# Spectacle_Director_Board.net
KiCad netlist of a schematic drawn in EAGLE
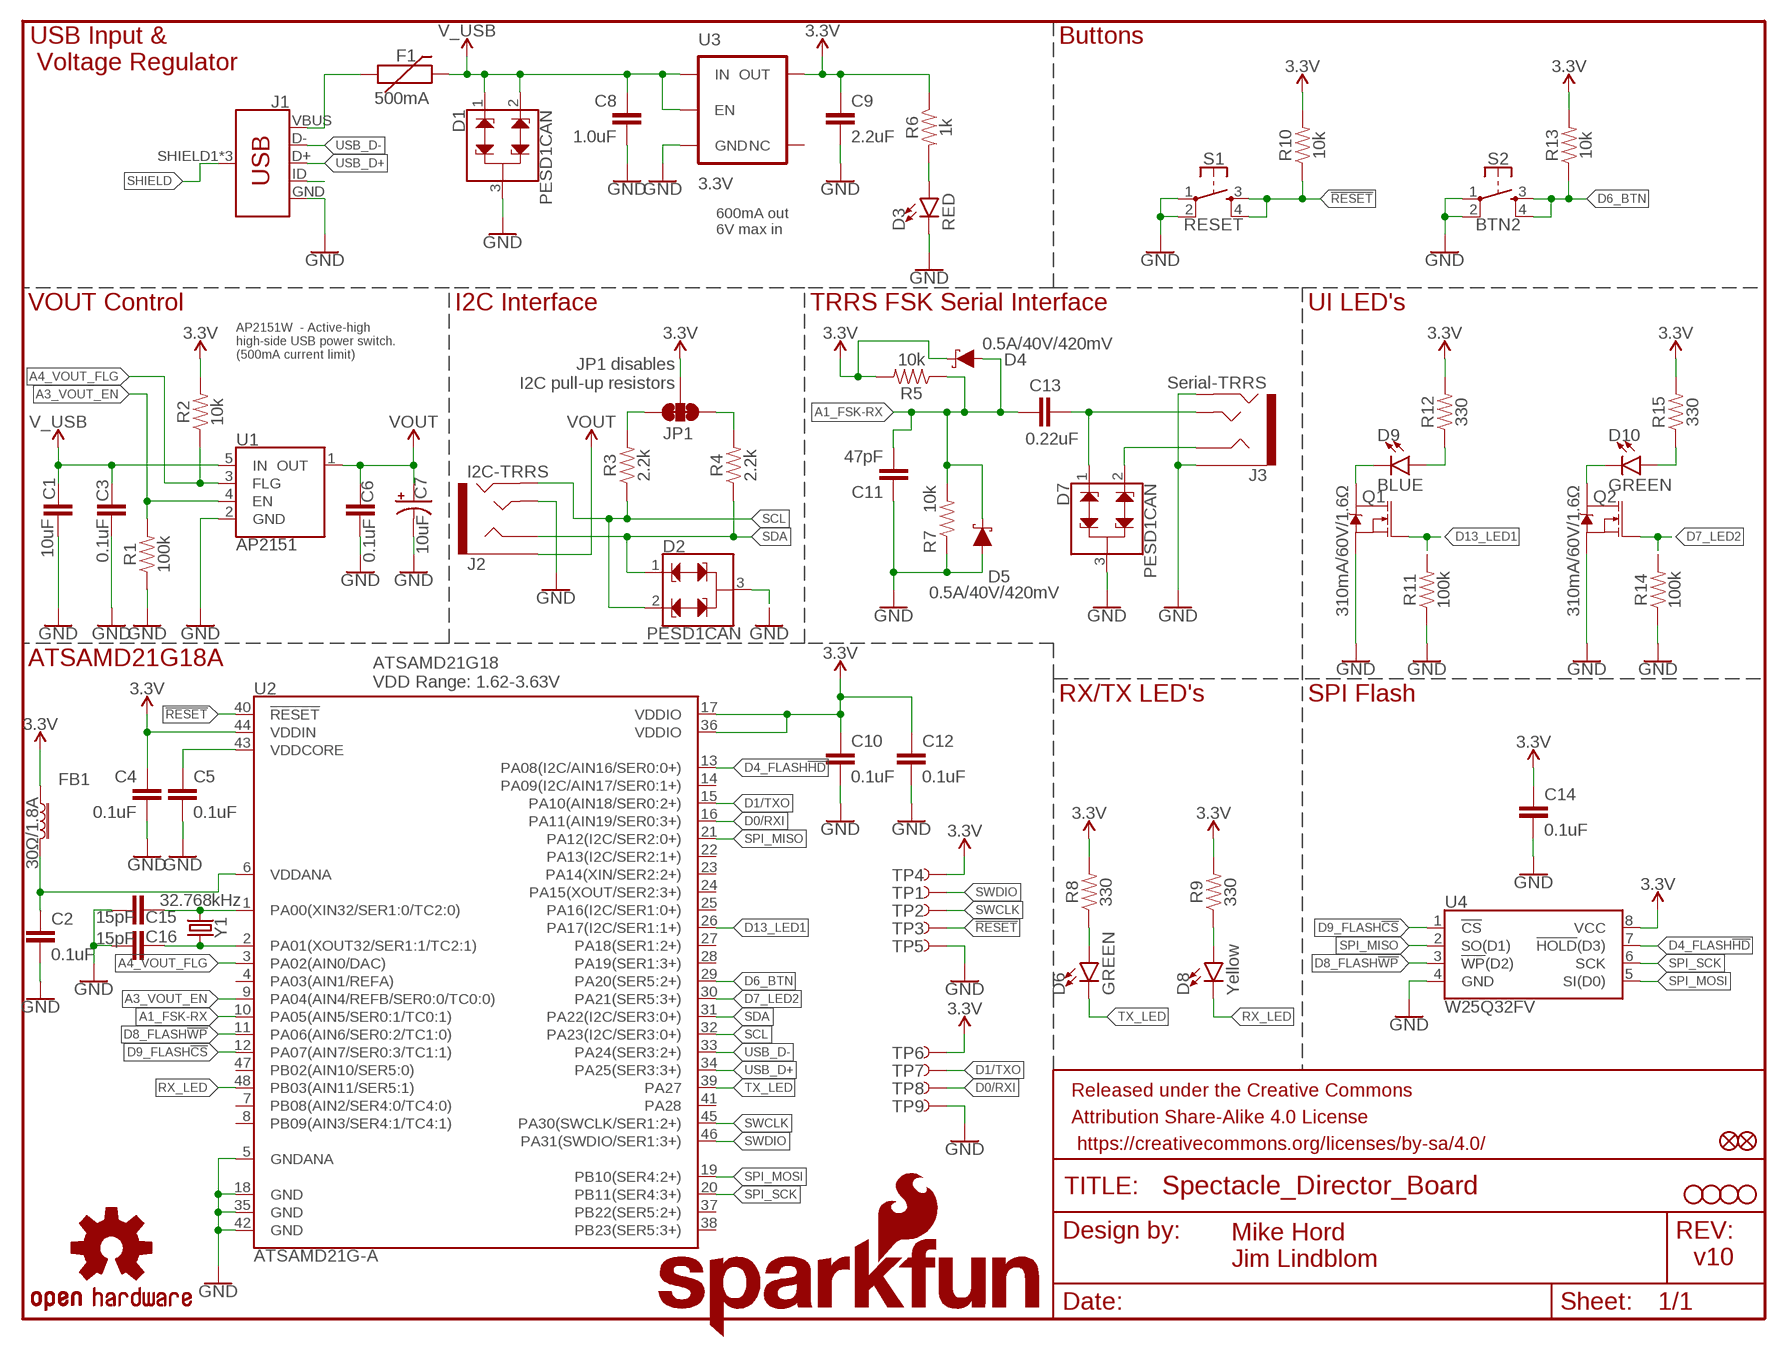
[diagram p0: schematic, sheet 1]

(export (version "E")
  (design (tool "Eeschema 10.0.6"))
  (components
    (comp (ref "C1")
      (value "10uF")
      (footprint "eagle-import:0805")
      (libsource (lib "eagle-import") (part "10UF-0805-10V-10%"))
    )
    (comp (ref "C2")
      (value "0.1uF")
      (footprint "eagle-import:0603")
      (libsource (lib "eagle-import") (part "0.1UF-0603-25V-(+80/-20%)"))
    )
    (comp (ref "C3")
      (value "0.1uF")
      (footprint "eagle-import:0603")
      (libsource (lib "eagle-import") (part "0.1UF-0603-25V-(+80/-20%)"))
    )
    (comp (ref "C4")
      (value "0.1uF")
      (footprint "eagle-import:0603")
      (libsource (lib "eagle-import") (part "0.1UF-0603-25V-(+80/-20%)"))
    )
    (comp (ref "C5")
      (value "0.1uF")
      (footprint "eagle-import:0603")
      (libsource (lib "eagle-import") (part "0.1UF-0603-25V-(+80/-20%)"))
    )
    (comp (ref "C6")
      (value "0.1uF")
      (footprint "eagle-import:0603")
      (libsource (lib "eagle-import") (part "0.1UF-0603-25V-(+80/-20%)"))
    )
    (comp (ref "C7")
      (value "10uF")
      (footprint "eagle-import:EIA3216")
      (libsource (lib "eagle-import") (part "10UF-POLAR-EIA3216-16V-10%(TANT)"))
    )
    (comp (ref "C8")
      (value "1.0uF")
      (footprint "eagle-import:0805")
      (libsource (lib "eagle-import") (part "1.0UF-0805-25V-(+80/-20%)"))
    )
    (comp (ref "C9")
      (value "2.2uF")
      (footprint "eagle-import:0603")
      (libsource (lib "eagle-import") (part "2.2UF-0603-10V-20%"))
    )
    (comp (ref "C10")
      (value "0.1uF")
      (footprint "eagle-import:0603")
      (libsource (lib "eagle-import") (part "0.1UF-0603-25V-(+80/-20%)"))
    )
    (comp (ref "C11")
      (value "47pF")
      (footprint "eagle-import:0603")
      (libsource (lib "eagle-import") (part "47PF-0603-50V-5%"))
    )
    (comp (ref "C12")
      (value "0.1uF")
      (footprint "eagle-import:0603")
      (libsource (lib "eagle-import") (part "0.1UF-0603-25V-(+80/-20%)"))
    )
    (comp (ref "C13")
      (value "0.22uF")
      (footprint "eagle-import:0603")
      (libsource (lib "eagle-import") (part "0.22UF-0603-25V-10%"))
    )
    (comp (ref "C14")
      (value "0.1uF")
      (footprint "eagle-import:0603")
      (libsource (lib "eagle-import") (part "0.1UF-0603-25V-(+80/-20%)"))
    )
    (comp (ref "C15")
      (value "15pF")
      (footprint "eagle-import:0603")
      (libsource (lib "eagle-import") (part "15PF-0603-50V-5%"))
    )
    (comp (ref "C16")
      (value "15pF")
      (footprint "eagle-import:0603")
      (libsource (lib "eagle-import") (part "15PF-0603-50V-5%"))
    )
    (comp (ref "D1")
      (value "PESD1CAN")
      (footprint "eagle-import:SOT23-3")
      (libsource (lib "eagle-import") (part "PESD1CAN"))
    )
    (comp (ref "D2")
      (value "PESD1CAN")
      (footprint "eagle-import:SOT23-3")
      (libsource (lib "eagle-import") (part "PESD1CAN"))
    )
    (comp (ref "D3")
      (value "RED")
      (footprint "eagle-import:LED-0603")
      (libsource (lib "eagle-import") (part "LED-RED0603"))
    )
    (comp (ref "D4")
      (value "0.5A/40V/420mV")
      (footprint "eagle-import:SOD-323")
      (libsource (lib "eagle-import") (part "DIODE-SCHOTTKY-PMEG4005EJ"))
    )
    (comp (ref "D5")
      (value "0.5A/40V/420mV")
      (footprint "eagle-import:SOD-323")
      (libsource (lib "eagle-import") (part "DIODE-SCHOTTKY-PMEG4005EJ"))
    )
    (comp (ref "D6")
      (value "GREEN")
      (footprint "eagle-import:LED-0603")
      (libsource (lib "eagle-import") (part "LED-GREEN0603"))
    )
    (comp (ref "D7")
      (value "PESD1CAN")
      (footprint "eagle-import:SOT23-3")
      (libsource (lib "eagle-import") (part "PESD1CAN"))
    )
    (comp (ref "D8")
      (value "Yellow")
      (footprint "eagle-import:LED-0603")
      (libsource (lib "eagle-import") (part "LED-YELLOW0603"))
    )
    (comp (ref "D9")
      (value "BLUE")
      (footprint "eagle-import:LED-0603")
      (libsource (lib "eagle-import") (part "LED-BLUE0603"))
    )
    (comp (ref "D10")
      (value "GREEN")
      (footprint "eagle-import:LED-0603")
      (libsource (lib "eagle-import") (part "LED-GREEN0603"))
    )
    (comp (ref "F1")
      (value "500mA")
      (footprint "eagle-import:PTC-1206")
      (libsource (lib "eagle-import") (part "PTCSMD"))
    )
    (comp (ref "FB1")
      (value "30Ω/1.8A")
      (footprint "eagle-import:0603")
      (libsource (lib "eagle-import") (part "FERRITE_BEAD-0603"))
    )
    (comp (ref "FD1")
      (value "FIDUCIALUFIDUCIAL")
      (footprint "eagle-import:FIDUCIAL-MICRO")
      (libsource (lib "eagle-import") (part "FIDUCIALUFIDUCIAL"))
    )
    (comp (ref "FD2")
      (value "FIDUCIALUFIDUCIAL")
      (footprint "eagle-import:FIDUCIAL-MICRO")
      (libsource (lib "eagle-import") (part "FIDUCIALUFIDUCIAL"))
    )
    (comp (ref "FRAME1")
      (value "FRAME-LETTER")
      (footprint "eagle-import:CREATIVE_COMMONS")
      (libsource (lib "eagle-import") (part "FRAME-LETTER"))
    )
    (comp (ref "H1")
      (value "STAND-OFF")
      (footprint "eagle-import:STAND-OFF")
      (libsource (lib "eagle-import") (part "STAND-OFF"))
    )
    (comp (ref "H2")
      (value "STAND-OFF")
      (footprint "eagle-import:STAND-OFF")
      (libsource (lib "eagle-import") (part "STAND-OFF"))
    )
    (comp (ref "H3")
      (value "STAND-OFF")
      (footprint "eagle-import:STAND-OFF")
      (libsource (lib "eagle-import") (part "STAND-OFF"))
    )
    (comp (ref "H4")
      (value "STAND-OFF")
      (footprint "eagle-import:STAND-OFF")
      (libsource (lib "eagle-import") (part "STAND-OFF"))
    )
    (comp (ref "J1")
      (value "USB_MICRO-B_FEMALE-SMT")
      (footprint "eagle-import:USB-B-MICRO-SMD")
      (libsource (lib "eagle-import") (part "USB_MICRO-B_FEMALE-SMT"))
    )
    (comp (ref "J2")
      (value "I2C-TRRS")
      (footprint "eagle-import:AUDIO_JACK_3.5MM_TRRS_SMD_RA")
      (libsource (lib "eagle-import") (part "AUDIO_JACK_TRRSSMD_RA"))
    )
    (comp (ref "J3")
      (value "Serial-TRRS")
      (footprint "eagle-import:AUDIO_JACK_3.5MM_TRRS_SMD_RA")
      (libsource (lib "eagle-import") (part "AUDIO_JACK_TRRSSMD_RA"))
    )
    (comp (ref "JP1")
      (value "JUMPER-SMT_3_2-NC_TRACE_NO-SILK")
      (footprint "eagle-import:SMT-JUMPER_3_2-NC_TRACE_NO-SILK")
      (libsource (lib "eagle-import") (part "JUMPER-SMT_3_2-NC_TRACE_NO-SILK"))
    )
    (comp (ref "LOGO1")
      (value "OSHW-LOGOMINI")
      (footprint "eagle-import:OSHW-LOGO-MINI")
      (libsource (lib "eagle-import") (part "OSHW-LOGOMINI"))
    )
    (comp (ref "LOGO2")
      (value "SFE_LOGO_NAME.2_INCH")
      (footprint "eagle-import:SFE_LOGO_NAME_.2")
      (libsource (lib "eagle-import") (part "SFE_LOGO_NAME.2_INCH"))
    )
    (comp (ref "LOGO3")
      (value "SFE_LOGO_FLAME.1COP")
      (footprint "eagle-import:SFE_LOGO_FLAME_COPPER_.1")
      (libsource (lib "eagle-import") (part "SFE_LOGO_FLAME.1COP"))
    )
    (comp (ref "Q1")
      (value "310mA/60V/1.6Ω")
      (footprint "eagle-import:SOT323")
      (libsource (lib "eagle-import") (part "MOSFET-NCH-2N7002PW"))
    )
    (comp (ref "Q2")
      (value "310mA/60V/1.6Ω")
      (footprint "eagle-import:SOT323")
      (libsource (lib "eagle-import") (part "MOSFET-NCH-2N7002PW"))
    )
    (comp (ref "R1")
      (value "100k")
      (footprint "eagle-import:0603")
      (libsource (lib "eagle-import") (part "100KOHM-0603-1/10W-1%"))
    )
    (comp (ref "R2")
      (value "10k")
      (footprint "eagle-import:0603")
      (libsource (lib "eagle-import") (part "10KOHM-0603-1/10W-1%"))
    )
    (comp (ref "R3")
      (value "2.2k")
      (footprint "eagle-import:0603")
      (libsource (lib "eagle-import") (part "2.2KOHM-0603-1/10W-1%"))
    )
    (comp (ref "R4")
      (value "2.2k")
      (footprint "eagle-import:0603")
      (libsource (lib "eagle-import") (part "2.2KOHM-0603-1/10W-1%"))
    )
    (comp (ref "R5")
      (value "10k")
      (footprint "eagle-import:0603")
      (libsource (lib "eagle-import") (part "10KOHM-0603-1/10W-1%"))
    )
    (comp (ref "R6")
      (value "1k")
      (footprint "eagle-import:0603")
      (libsource (lib "eagle-import") (part "1KOHM-0603-1/10W-1%"))
    )
    (comp (ref "R7")
      (value "10k")
      (footprint "eagle-import:0603")
      (libsource (lib "eagle-import") (part "10KOHM-0603-1/10W-1%"))
    )
    (comp (ref "R8")
      (value "330")
      (footprint "eagle-import:0603")
      (libsource (lib "eagle-import") (part "330OHM-0603-1/10W-1%"))
    )
    (comp (ref "R9")
      (value "330")
      (footprint "eagle-import:0603")
      (libsource (lib "eagle-import") (part "330OHM-0603-1/10W-1%"))
    )
    (comp (ref "R10")
      (value "10k")
      (footprint "eagle-import:0603")
      (libsource (lib "eagle-import") (part "10KOHM-0603-1/10W-1%"))
    )
    (comp (ref "R11")
      (value "100k")
      (footprint "eagle-import:0603")
      (libsource (lib "eagle-import") (part "100KOHM-0603-1/10W-1%"))
    )
    (comp (ref "R12")
      (value "330")
      (footprint "eagle-import:0603")
      (libsource (lib "eagle-import") (part "330OHM-0603-1/10W-1%"))
    )
    (comp (ref "R13")
      (value "10k")
      (footprint "eagle-import:0603")
      (libsource (lib "eagle-import") (part "10KOHM-0603-1/10W-1%"))
    )
    (comp (ref "R14")
      (value "100k")
      (footprint "eagle-import:0603")
      (libsource (lib "eagle-import") (part "100KOHM-0603-1/10W-1%"))
    )
    (comp (ref "R15")
      (value "330")
      (footprint "eagle-import:0603")
      (libsource (lib "eagle-import") (part "330OHM-0603-1/10W-1%"))
    )
    (comp (ref "S1")
      (value "RESET")
      (footprint "eagle-import:TACTILE_SWITCH_SMD_4.6X2.8MM")
      (libsource (lib "eagle-import") (part "MOMENTARY-SWITCH-SPST-2-SMD-4.6X2.8MM"))
    )
    (comp (ref "S2")
      (value "BTN2")
      (footprint "eagle-import:TACTILE_SWITCH_SMD_4.6X2.8MM")
      (libsource (lib "eagle-import") (part "MOMENTARY-SWITCH-SPST-2-SMD-4.6X2.8MM"))
    )
    (comp (ref "TP1")
      (value "TP-SWDIO")
      (footprint "eagle-import:PAD.03X.05")
      (libsource (lib "eagle-import") (part "TEST-POINT3X5"))
    )
    (comp (ref "TP2")
      (value "TP-SWCLK")
      (footprint "eagle-import:PAD.03X.05")
      (libsource (lib "eagle-import") (part "TEST-POINT3X5"))
    )
    (comp (ref "TP3")
      (value "TP-!RESET!")
      (footprint "eagle-import:PAD.03X.05")
      (libsource (lib "eagle-import") (part "TEST-POINT3X5"))
    )
    (comp (ref "TP4")
      (value "TP-3.3V")
      (footprint "eagle-import:PAD.03X.05")
      (libsource (lib "eagle-import") (part "TEST-POINT3X5"))
    )
    (comp (ref "TP5")
      (value "TP-GND")
      (footprint "eagle-import:PAD.03X.05")
      (libsource (lib "eagle-import") (part "TEST-POINT3X5"))
    )
    (comp (ref "TP6")
      (value "TP-GND")
      (footprint "eagle-import:PAD.03X.05")
      (libsource (lib "eagle-import") (part "TEST-POINT3X5"))
    )
    (comp (ref "TP7")
      (value "TP-GND")
      (footprint "eagle-import:PAD.03X.05")
      (libsource (lib "eagle-import") (part "TEST-POINT3X5"))
    )
    (comp (ref "TP8")
      (value "TP-GND")
      (footprint "eagle-import:PAD.03X.05")
      (libsource (lib "eagle-import") (part "TEST-POINT3X5"))
    )
    (comp (ref "TP9")
      (value "TP-GND")
      (footprint "eagle-import:PAD.03X.05")
      (libsource (lib "eagle-import") (part "TEST-POINT3X5"))
    )
    (comp (ref "U1")
      (value "AP2151")
      (footprint "eagle-import:SOT23-5")
      (libsource (lib "eagle-import") (part "AP2151W"))
    )
    (comp (ref "U2")
      (value "ATSAMD21G-A")
      (footprint "eagle-import:TQFP-48")
      (libsource (lib "eagle-import") (part "ATSAMD21G-A"))
    )
    (comp (ref "U3")
      (value "3.3V")
      (footprint "eagle-import:SOT23-5")
      (fields (field (name "PROD_ID") "VREG-12457"))
      (libsource (lib "eagle-import") (part "V_REG_AP2112K-3.3V"))
    )
    (comp (ref "U4")
      (value "W25Q32FV")
      (footprint "eagle-import:SOIC-8")
      (libsource (lib "eagle-import") (part "W25Q32FVSS"))
    )
    (comp (ref "Y1")
      (value "32.768kHz")
      (footprint "eagle-import:CRYSTAL-SMD-3.2X1.5MM")
      (libsource (lib "eagle-import") (part "CRYSTAL-32.768KHZSMD-3.2X1.5"))
    )
  )
  (nets
    (net (code "1") (name "/D4_FLASH~{HD}") (class "Default")
      (node (ref "U2") (pin "13") (pinfunction "PA08(I2C/AIN16/SER0:0+)_13") (pintype "bidirectional"))
      (node (ref "U4") (pin "7") (pinfunction "~{HOLD}(D3)_7") (pintype "bidirectional"))
    )
    (net (code "2") (name "/D8_FLASH~{WP}") (class "Default")
      (node (ref "U2") (pin "11") (pinfunction "PA06(AIN6/SER0:2/TC1:0)_11") (pintype "bidirectional"))
      (node (ref "U4") (pin "3") (pinfunction "~{WP}(D2)_3") (pintype "bidirectional"))
    )
    (net (code "3") (name "/D9_FLASH~{CS}") (class "Default")
      (node (ref "U2") (pin "12") (pinfunction "PA07(AIN7/SER0:3/TC1:1)_12") (pintype "bidirectional"))
      (node (ref "U4") (pin "1") (pinfunction "~{CS}_1") (pintype "bidirectional"))
    )
    (net (code "4") (name "/~{RESET}") (class "Default")
      (node (ref "R10") (pin "1") (pinfunction "1_1") (pintype "passive"))
      (node (ref "S1") (pin "3") (pinfunction "3_3") (pintype "passive"))
      (node (ref "S1") (pin "4") (pinfunction "4_4") (pintype "passive"))
      (node (ref "TP3") (pin "P$1") (pinfunction "1_P$1") (pintype "bidirectional"))
      (node (ref "U2") (pin "40") (pinfunction "~{RESET}_40") (pintype "bidirectional"))
    )
    (net (code "5") (name "3.3V") (class "Default")
      (node (ref "C10") (pin "1") (pinfunction "1_1") (pintype "passive"))
      (node (ref "C12") (pin "1") (pinfunction "1_1") (pintype "passive"))
      (node (ref "C14") (pin "1") (pinfunction "1_1") (pintype "passive"))
      (node (ref "C4") (pin "1") (pinfunction "1_1") (pintype "passive"))
      (node (ref "C9") (pin "1") (pinfunction "1_1") (pintype "passive"))
      (node (ref "D4") (pin "C") (pinfunction "C_C") (pintype "passive"))
      (node (ref "FB1") (pin "1") (pinfunction "1_1") (pintype "passive"))
      (node (ref "JP1") (pin "2") (pinfunction "2_2") (pintype "passive"))
      (node (ref "R10") (pin "2") (pinfunction "2_2") (pintype "passive"))
      (node (ref "R12") (pin "2") (pinfunction "2_2") (pintype "passive"))
      (node (ref "R13") (pin "2") (pinfunction "2_2") (pintype "passive"))
      (node (ref "R15") (pin "2") (pinfunction "2_2") (pintype "passive"))
      (node (ref "R2") (pin "2") (pinfunction "2_2") (pintype "passive"))
      (node (ref "R5") (pin "2") (pinfunction "2_2") (pintype "passive"))
      (node (ref "R6") (pin "1") (pinfunction "1_1") (pintype "passive"))
      (node (ref "R8") (pin "2") (pinfunction "2_2") (pintype "passive"))
      (node (ref "R9") (pin "2") (pinfunction "2_2") (pintype "passive"))
      (node (ref "TP4") (pin "P$1") (pinfunction "1_P$1") (pintype "bidirectional"))
      (node (ref "TP6") (pin "P$1") (pinfunction "1_P$1") (pintype "bidirectional"))
      (node (ref "U2") (pin "17") (pinfunction "VDDIO_17") (pintype "bidirectional"))
      (node (ref "U2") (pin "36") (pinfunction "VDDIO_36") (pintype "bidirectional"))
      (node (ref "U2") (pin "44") (pinfunction "VDDIN_44") (pintype "bidirectional"))
      (node (ref "U3") (pin "5") (pinfunction "OUT_5") (pintype "passive"))
      (node (ref "U4") (pin "8") (pinfunction "VCC_8") (pintype "bidirectional"))
    )
    (net (code "6") (name "A1_FSK-RX") (class "Default")
      (node (ref "C11") (pin "2") (pinfunction "2_2") (pintype "passive"))
      (node (ref "C13") (pin "1") (pinfunction "1_1") (pintype "passive"))
      (node (ref "D4") (pin "A") (pinfunction "A_A") (pintype "passive"))
      (node (ref "D5") (pin "C") (pinfunction "C_C") (pintype "passive"))
      (node (ref "R5") (pin "1") (pinfunction "1_1") (pintype "passive"))
      (node (ref "R7") (pin "2") (pinfunction "2_2") (pintype "passive"))
      (node (ref "U2") (pin "10") (pinfunction "PA05(AIN5/SER0:1/TC0:1)_10") (pintype "bidirectional"))
    )
    (net (code "7") (name "A3_VOUT_EN") (class "Default")
      (node (ref "R1") (pin "2") (pinfunction "2_2") (pintype "passive"))
      (node (ref "U1") (pin "4") (pinfunction "EN_4") (pintype "bidirectional"))
      (node (ref "U2") (pin "9") (pinfunction "PA04(AIN4/REFB/SER0:0/TC0:0)_9") (pintype "bidirectional"))
    )
    (net (code "8") (name "A4_VOUT_FLG") (class "Default")
      (node (ref "R2") (pin "1") (pinfunction "1_1") (pintype "passive"))
      (node (ref "U1") (pin "3") (pinfunction "FLG_3") (pintype "bidirectional"))
      (node (ref "U2") (pin "3") (pinfunction "PA02(AIN0/DAC)_3") (pintype "bidirectional"))
    )
    (net (code "9") (name "D0{slash}RXI") (class "Default")
      (node (ref "TP8") (pin "P$1") (pinfunction "1_P$1") (pintype "bidirectional"))
      (node (ref "U2") (pin "16") (pinfunction "PA11(AIN19/SER0:3+)_16") (pintype "bidirectional"))
    )
    (net (code "10") (name "D1{slash}TXO") (class "Default")
      (node (ref "TP7") (pin "P$1") (pinfunction "1_P$1") (pintype "bidirectional"))
      (node (ref "U2") (pin "15") (pinfunction "PA10(AIN18/SER0:2+)_15") (pintype "bidirectional"))
    )
    (net (code "11") (name "D6_BTN") (class "Default")
      (node (ref "R13") (pin "1") (pinfunction "1_1") (pintype "passive"))
      (node (ref "S2") (pin "3") (pinfunction "3_3") (pintype "passive"))
      (node (ref "S2") (pin "4") (pinfunction "4_4") (pintype "passive"))
      (node (ref "U2") (pin "29") (pinfunction "PA20(SER5:2+)_29") (pintype "bidirectional"))
    )
    (net (code "12") (name "D7_LED2") (class "Default")
      (node (ref "Q2") (pin "1") (pinfunction "G_1") (pintype "bidirectional"))
      (node (ref "R14") (pin "2") (pinfunction "2_2") (pintype "passive"))
      (node (ref "U2") (pin "30") (pinfunction "PA21(SER5:3+)_30") (pintype "bidirectional"))
    )
    (net (code "13") (name "D13_LED1") (class "Default")
      (node (ref "Q1") (pin "1") (pinfunction "G_1") (pintype "bidirectional"))
      (node (ref "R11") (pin "2") (pinfunction "2_2") (pintype "passive"))
      (node (ref "U2") (pin "26") (pinfunction "PA17(I2C/SER1:1+)_26") (pintype "bidirectional"))
    )
    (net (code "14") (name "GND") (class "Default")
      (node (ref "C1") (pin "2") (pinfunction "2_2") (pintype "passive"))
      (node (ref "C10") (pin "2") (pinfunction "2_2") (pintype "passive"))
      (node (ref "C11") (pin "1") (pinfunction "1_1") (pintype "passive"))
      (node (ref "C12") (pin "2") (pinfunction "2_2") (pintype "passive"))
      (node (ref "C14") (pin "2") (pinfunction "2_2") (pintype "passive"))
      (node (ref "C15") (pin "1") (pinfunction "1_1") (pintype "passive"))
      (node (ref "C16") (pin "1") (pinfunction "1_1") (pintype "passive"))
      (node (ref "C2") (pin "2") (pinfunction "2_2") (pintype "passive"))
      (node (ref "C3") (pin "2") (pinfunction "2_2") (pintype "passive"))
      (node (ref "C4") (pin "2") (pinfunction "2_2") (pintype "passive"))
      (node (ref "C5") (pin "2") (pinfunction "2_2") (pintype "passive"))
      (node (ref "C6") (pin "2") (pinfunction "2_2") (pintype "passive"))
      (node (ref "C7") (pin "-") (pinfunction "-_-") (pintype "passive"))
      (node (ref "C8") (pin "2") (pinfunction "2_2") (pintype "passive"))
      (node (ref "C9") (pin "2") (pinfunction "2_2") (pintype "passive"))
      (node (ref "D1") (pin "3") (pinfunction "3_3") (pintype "bidirectional"))
      (node (ref "D2") (pin "3") (pinfunction "3_3") (pintype "bidirectional"))
      (node (ref "D3") (pin "C") (pinfunction "C_C") (pintype "passive"))
      (node (ref "D5") (pin "A") (pinfunction "A_A") (pintype "passive"))
      (node (ref "D7") (pin "3") (pinfunction "3_3") (pintype "bidirectional"))
      (node (ref "J1") (pin "GND") (pinfunction "GND_GND") (pintype "power_in"))
      (node (ref "J2") (pin "TIP") (pinfunction "TIP_TIP") (pintype "bidirectional"))
      (node (ref "J3") (pin "EARTH") (pinfunction "EARTH_EARTH") (pintype "bidirectional"))
      (node (ref "J3") (pin "RING2") (pinfunction "RING2_RING2") (pintype "bidirectional"))
      (node (ref "Q1") (pin "2") (pinfunction "S_2") (pintype "bidirectional"))
      (node (ref "Q2") (pin "2") (pinfunction "S_2") (pintype "bidirectional"))
      (node (ref "R1") (pin "1") (pinfunction "1_1") (pintype "passive"))
      (node (ref "R11") (pin "1") (pinfunction "1_1") (pintype "passive"))
      (node (ref "R14") (pin "1") (pinfunction "1_1") (pintype "passive"))
      (node (ref "R7") (pin "1") (pinfunction "1_1") (pintype "passive"))
      (node (ref "S1") (pin "1") (pinfunction "1_1") (pintype "passive"))
      (node (ref "S1") (pin "2") (pinfunction "2_2") (pintype "passive"))
      (node (ref "S2") (pin "1") (pinfunction "1_1") (pintype "passive"))
      (node (ref "S2") (pin "2") (pinfunction "2_2") (pintype "passive"))
      (node (ref "TP5") (pin "P$1") (pinfunction "1_P$1") (pintype "bidirectional"))
      (node (ref "TP9") (pin "P$1") (pinfunction "1_P$1") (pintype "bidirectional"))
      (node (ref "U1") (pin "2") (pinfunction "GND_2") (pintype "bidirectional"))
      (node (ref "U2") (pin "18") (pinfunction "GND_18") (pintype "bidirectional"))
      (node (ref "U2") (pin "35") (pinfunction "GND_35") (pintype "bidirectional"))
      (node (ref "U2") (pin "42") (pinfunction "GND_42") (pintype "bidirectional"))
      (node (ref "U2") (pin "5") (pinfunction "GNDANA_5") (pintype "bidirectional"))
      (node (ref "U3") (pin "2") (pinfunction "GND_2") (pintype "input"))
      (node (ref "U4") (pin "4") (pinfunction "GND_4") (pintype "bidirectional"))
    )
    (net (code "15") (name "Net-(C13-Pad2)") (class "Default")
      (node (ref "C13") (pin "2") (pinfunction "2_2") (pintype "passive"))
      (node (ref "D7") (pin "1") (pinfunction "1_1") (pintype "bidirectional"))
      (node (ref "J3") (pin "TIP") (pinfunction "TIP_TIP") (pintype "bidirectional"))
    )
    (net (code "16") (name "Net-(D3-PadA)") (class "Default")
      (node (ref "D3") (pin "A") (pinfunction "A_A") (pintype "passive"))
      (node (ref "R6") (pin "2") (pinfunction "2_2") (pintype "passive"))
    )
    (net (code "17") (name "Net-(D6-PadA)") (class "Default")
      (node (ref "D6") (pin "A") (pinfunction "A_A") (pintype "passive"))
      (node (ref "R8") (pin "1") (pinfunction "1_1") (pintype "passive"))
    )
    (net (code "18") (name "Net-(D7-Pad2)") (class "Default")
      (node (ref "D7") (pin "2") (pinfunction "2_2") (pintype "bidirectional"))
      (node (ref "J3") (pin "RING1") (pinfunction "RING1_RING1") (pintype "bidirectional"))
    )
    (net (code "19") (name "Net-(D8-PadA)") (class "Default")
      (node (ref "D8") (pin "A") (pinfunction "A_A") (pintype "passive"))
      (node (ref "R9") (pin "1") (pinfunction "1_1") (pintype "passive"))
    )
    (net (code "20") (name "Net-(D9-PadA)") (class "Default")
      (node (ref "D9") (pin "A") (pinfunction "A_A") (pintype "passive"))
      (node (ref "R12") (pin "1") (pinfunction "1_1") (pintype "passive"))
    )
    (net (code "21") (name "Net-(D10-PadA)") (class "Default")
      (node (ref "D10") (pin "A") (pinfunction "A_A") (pintype "passive"))
      (node (ref "R15") (pin "1") (pinfunction "1_1") (pintype "passive"))
    )
    (net (code "22") (name "Net-(F1-Pad1)") (class "Default")
      (node (ref "F1") (pin "1") (pinfunction "1_1") (pintype "bidirectional"))
      (node (ref "J1") (pin "VBUS") (pinfunction "VBUS_VBUS") (pintype "power_in"))
    )
    (net (code "23") (name "Net-(JP1-Pad1)") (class "Default")
      (node (ref "JP1") (pin "1") (pinfunction "1_1") (pintype "passive"))
      (node (ref "R4") (pin "2") (pinfunction "2_2") (pintype "passive"))
    )
    (net (code "24") (name "Net-(JP1-Pad3)") (class "Default")
      (node (ref "JP1") (pin "3") (pinfunction "3_3") (pintype "passive"))
      (node (ref "R3") (pin "2") (pinfunction "2_2") (pintype "passive"))
    )
    (net (code "25") (name "Net-(Q1-D)") (class "Default")
      (node (ref "D9") (pin "C") (pinfunction "C_C") (pintype "passive"))
      (node (ref "Q1") (pin "3") (pinfunction "D_3") (pintype "bidirectional"))
    )
    (net (code "26") (name "Net-(Q2-D)") (class "Default")
      (node (ref "D10") (pin "C") (pinfunction "C_C") (pintype "passive"))
      (node (ref "Q2") (pin "3") (pinfunction "D_3") (pintype "bidirectional"))
    )
    (net (code "27") (name "Net-(U2-PA00(XIN32{slash}SER1:0{slash}TC2:0))") (class "Default")
      (node (ref "C15") (pin "2") (pinfunction "2_2") (pintype "passive"))
      (node (ref "U2") (pin "1") (pinfunction "PA00(XIN32/SER1:0/TC2:0)_1") (pintype "bidirectional"))
      (node (ref "Y1") (pin "P$2") (pinfunction "2_P$2") (pintype "passive"))
    )
    (net (code "28") (name "Net-(U2-PA01(XOUT32{slash}SER1:1{slash}TC2:1))") (class "Default")
      (node (ref "C16") (pin "2") (pinfunction "2_2") (pintype "passive"))
      (node (ref "U2") (pin "2") (pinfunction "PA01(XOUT32/SER1:1/TC2:1)_2") (pintype "bidirectional"))
      (node (ref "Y1") (pin "P$1") (pinfunction "1_P$1") (pintype "passive"))
    )
    (net (code "29") (name "Net-(U2-VDDANA)") (class "Default")
      (node (ref "C2") (pin "1") (pinfunction "1_1") (pintype "passive"))
      (node (ref "FB1") (pin "2") (pinfunction "2_2") (pintype "passive"))
      (node (ref "U2") (pin "6") (pinfunction "VDDANA_6") (pintype "bidirectional"))
    )
    (net (code "30") (name "Net-(U2-VDDCORE)") (class "Default")
      (node (ref "C5") (pin "1") (pinfunction "1_1") (pintype "passive"))
      (node (ref "U2") (pin "43") (pinfunction "VDDCORE_43") (pintype "bidirectional"))
    )
    (net (code "31") (name "RX_LED") (class "Default")
      (node (ref "D8") (pin "C") (pinfunction "C_C") (pintype "passive"))
      (node (ref "U2") (pin "48") (pinfunction "PB03(AIN11/SER5:1)_48") (pintype "bidirectional"))
    )
    (net (code "32") (name "SCL") (class "Default")
      (node (ref "D2") (pin "2") (pinfunction "2_2") (pintype "bidirectional"))
      (node (ref "J2") (pin "RING2") (pinfunction "RING2_RING2") (pintype "bidirectional"))
      (node (ref "R3") (pin "1") (pinfunction "1_1") (pintype "passive"))
      (node (ref "U2") (pin "32") (pinfunction "PA23(I2C/SER3:0+)_32") (pintype "bidirectional"))
    )
    (net (code "33") (name "SDA") (class "Default")
      (node (ref "D2") (pin "1") (pinfunction "1_1") (pintype "bidirectional"))
      (node (ref "J2") (pin "RING1") (pinfunction "RING1_RING1") (pintype "bidirectional"))
      (node (ref "R4") (pin "1") (pinfunction "1_1") (pintype "passive"))
      (node (ref "U2") (pin "31") (pinfunction "PA22(I2C/SER3:0+)_31") (pintype "bidirectional"))
    )
    (net (code "34") (name "SHIELD") (class "Default")
      (node (ref "J1") (pin "SHIELD1") (pinfunction "SHIELD_SHIELD1") (pintype "bidirectional"))
      (node (ref "J1") (pin "SHIELD2") (pinfunction "SHIELD_SHIELD2") (pintype "bidirectional"))
      (node (ref "J1") (pin "SHIELD3") (pinfunction "SHIELD_SHIELD3") (pintype "bidirectional"))
    )
    (net (code "35") (name "SPI_MISO") (class "Default")
      (node (ref "U2") (pin "21") (pinfunction "PA12(I2C/SER2:0+)_21") (pintype "bidirectional"))
      (node (ref "U4") (pin "2") (pinfunction "SO(D1)_2") (pintype "bidirectional"))
    )
    (net (code "36") (name "SPI_MOSI") (class "Default")
      (node (ref "U2") (pin "19") (pinfunction "PB10(SER4:2+)_19") (pintype "bidirectional"))
      (node (ref "U4") (pin "5") (pinfunction "SI(D0)_5") (pintype "bidirectional"))
    )
    (net (code "37") (name "SPI_SCK") (class "Default")
      (node (ref "U2") (pin "20") (pinfunction "PB11(SER4:3+)_20") (pintype "bidirectional"))
      (node (ref "U4") (pin "6") (pinfunction "SCK_6") (pintype "bidirectional"))
    )
    (net (code "38") (name "SWCLK") (class "Default")
      (node (ref "TP2") (pin "P$1") (pinfunction "1_P$1") (pintype "bidirectional"))
      (node (ref "U2") (pin "45") (pinfunction "PA30(SWCLK/SER1:2+)_45") (pintype "bidirectional"))
    )
    (net (code "39") (name "SWDIO") (class "Default")
      (node (ref "TP1") (pin "P$1") (pinfunction "1_P$1") (pintype "bidirectional"))
      (node (ref "U2") (pin "46") (pinfunction "PA31(SWDIO/SER1:3+)_46") (pintype "bidirectional"))
    )
    (net (code "40") (name "TX_LED") (class "Default")
      (node (ref "D6") (pin "C") (pinfunction "C_C") (pintype "passive"))
      (node (ref "U2") (pin "39") (pinfunction "PA27_39") (pintype "bidirectional"))
    )
    (net (code "41") (name "USB_D+") (class "Default")
      (node (ref "J1") (pin "D+") (pinfunction "D+_D+") (pintype "bidirectional"))
      (node (ref "U2") (pin "34") (pinfunction "PA25(SER3:3+)_34") (pintype "bidirectional"))
    )
    (net (code "42") (name "USB_D-") (class "Default")
      (node (ref "J1") (pin "D-") (pinfunction "D-_D-") (pintype "bidirectional"))
      (node (ref "U2") (pin "33") (pinfunction "PA24(SER3:2+)_33") (pintype "bidirectional"))
    )
    (net (code "43") (name "VOUT") (class "Default")
      (node (ref "C6") (pin "1") (pinfunction "1_1") (pintype "passive"))
      (node (ref "C7") (pin "+") (pinfunction "+_+") (pintype "passive"))
      (node (ref "J2") (pin "EARTH") (pinfunction "EARTH_EARTH") (pintype "bidirectional"))
      (node (ref "U1") (pin "1") (pinfunction "OUT_1") (pintype "bidirectional"))
    )
    (net (code "44") (name "V_USB") (class "Default")
      (node (ref "C1") (pin "1") (pinfunction "1_1") (pintype "passive"))
      (node (ref "C3") (pin "1") (pinfunction "1_1") (pintype "passive"))
      (node (ref "C8") (pin "1") (pinfunction "1_1") (pintype "passive"))
      (node (ref "D1") (pin "1") (pinfunction "1_1") (pintype "bidirectional"))
      (node (ref "D1") (pin "2") (pinfunction "2_2") (pintype "bidirectional"))
      (node (ref "F1") (pin "2") (pinfunction "2_2") (pintype "bidirectional"))
      (node (ref "U1") (pin "5") (pinfunction "IN_5") (pintype "bidirectional"))
      (node (ref "U3") (pin "1") (pinfunction "IN_1") (pintype "input"))
      (node (ref "U3") (pin "3") (pinfunction "EN_3") (pintype "input"))
    )
    (net (code "45") (name "unconnected-(J1-PadID)") (class "Default")
      (node (ref "J1") (pin "ID") (pinfunction "ID_ID") (pintype "bidirectional"))
    )
    (net (code "46") (name "unconnected-(U2-PA03(AIN1{slash}REFA)-Pad4)") (class "Default")
      (node (ref "U2") (pin "4") (pinfunction "PA03(AIN1/REFA)_4") (pintype "bidirectional"))
    )
    (net (code "47") (name "unconnected-(U2-PA09(I2C{slash}AIN17{slash}SER0:1+)-Pad14)") (class "Default")
      (node (ref "U2") (pin "14") (pinfunction "PA09(I2C/AIN17/SER0:1+)_14") (pintype "bidirectional"))
    )
    (net (code "48") (name "unconnected-(U2-PA13(I2C{slash}SER2:1+)-Pad22)") (class "Default")
      (node (ref "U2") (pin "22") (pinfunction "PA13(I2C/SER2:1+)_22") (pintype "bidirectional"))
    )
    (net (code "49") (name "unconnected-(U2-PA14(XIN{slash}SER2:2+)-Pad23)") (class "Default")
      (node (ref "U2") (pin "23") (pinfunction "PA14(XIN/SER2:2+)_23") (pintype "bidirectional"))
    )
    (net (code "50") (name "unconnected-(U2-PA15(XOUT{slash}SER2:3+)-Pad24)") (class "Default")
      (node (ref "U2") (pin "24") (pinfunction "PA15(XOUT/SER2:3+)_24") (pintype "bidirectional"))
    )
    (net (code "51") (name "unconnected-(U2-PA16(I2C{slash}SER1:0+)-Pad25)") (class "Default")
      (node (ref "U2") (pin "25") (pinfunction "PA16(I2C/SER1:0+)_25") (pintype "bidirectional"))
    )
    (net (code "52") (name "unconnected-(U2-PA18(SER1:2+)-Pad27)") (class "Default")
      (node (ref "U2") (pin "27") (pinfunction "PA18(SER1:2+)_27") (pintype "bidirectional"))
    )
    (net (code "53") (name "unconnected-(U2-PA19(SER1:3+)-Pad28)") (class "Default")
      (node (ref "U2") (pin "28") (pinfunction "PA19(SER1:3+)_28") (pintype "bidirectional"))
    )
    (net (code "54") (name "unconnected-(U2-PA28-Pad41)") (class "Default")
      (node (ref "U2") (pin "41") (pinfunction "PA28_41") (pintype "bidirectional"))
    )
    (net (code "55") (name "unconnected-(U2-PB02(AIN10{slash}SER5:0)-Pad47)") (class "Default")
      (node (ref "U2") (pin "47") (pinfunction "PB02(AIN10/SER5:0)_47") (pintype "bidirectional"))
    )
    (net (code "56") (name "unconnected-(U2-PB08(AIN2{slash}SER4:0{slash}TC4:0)-Pad7)") (class "Default")
      (node (ref "U2") (pin "7") (pinfunction "PB08(AIN2/SER4:0/TC4:0)_7") (pintype "bidirectional"))
    )
    (net (code "57") (name "unconnected-(U2-PB09(AIN3{slash}SER4:1{slash}TC4:1)-Pad8)") (class "Default")
      (node (ref "U2") (pin "8") (pinfunction "PB09(AIN3/SER4:1/TC4:1)_8") (pintype "bidirectional"))
    )
    (net (code "58") (name "unconnected-(U2-PB22(SER5:2+)-Pad37)") (class "Default")
      (node (ref "U2") (pin "37") (pinfunction "PB22(SER5:2+)_37") (pintype "bidirectional"))
    )
    (net (code "59") (name "unconnected-(U2-PB23(SER5:3+)-Pad38)") (class "Default")
      (node (ref "U2") (pin "38") (pinfunction "PB23(SER5:3+)_38") (pintype "bidirectional"))
    )
    (net (code "60") (name "unconnected-(U3-NC-Pad4)") (class "Default")
      (node (ref "U3") (pin "4") (pinfunction "NC_4") (pintype "input"))
    )
  )
)
